# STorM32_NT_breakout_v10.net
KiCad netlist of a schematic drawn in EAGLE
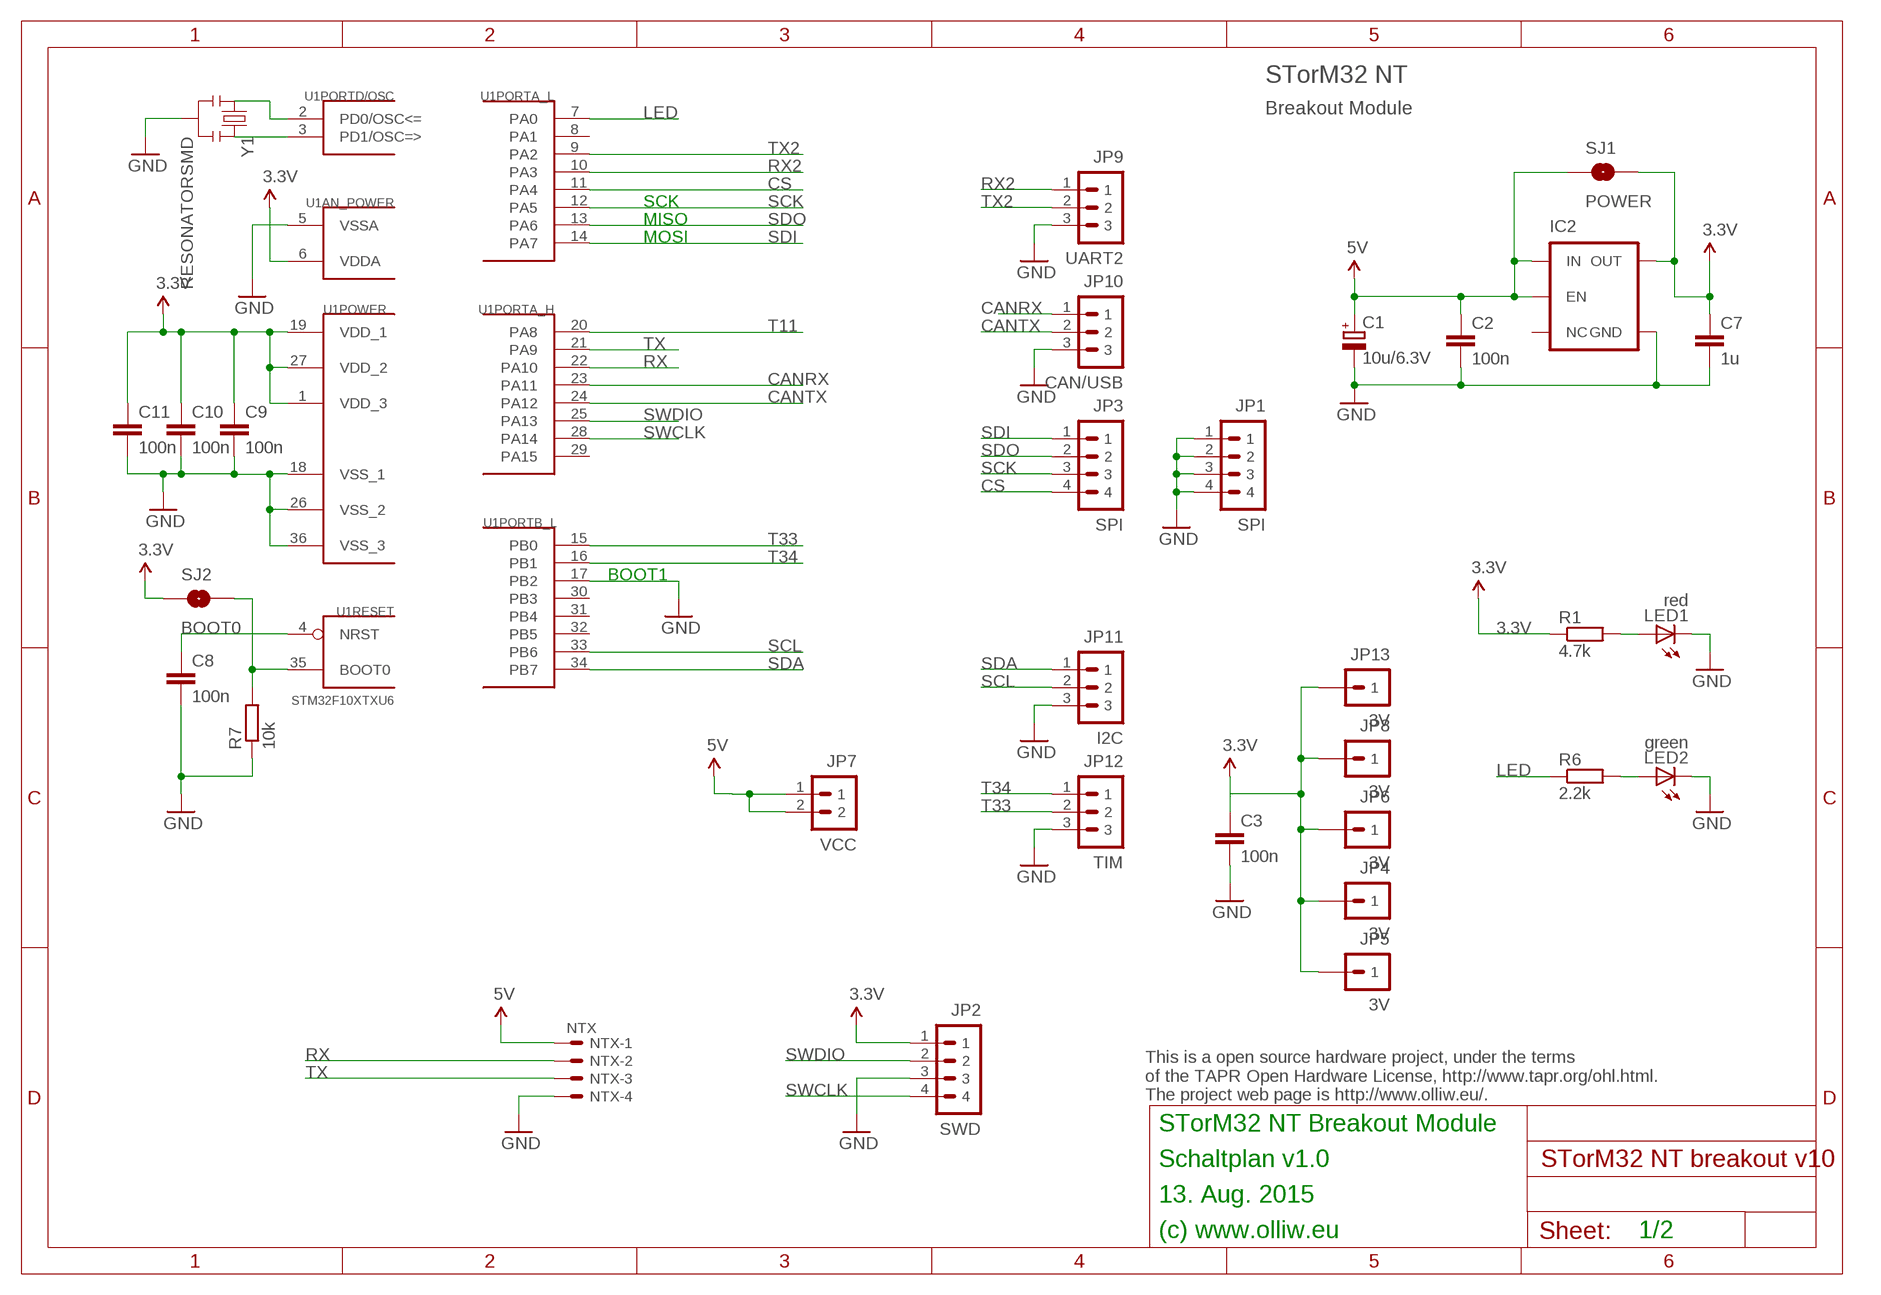
[diagram p0: schematic, sheet 1]

(export (version "E")
  (design (tool "Eeschema 10.0.6"))
  (components
    (comp (ref "C1")
      (value "10u/6.3V")
      (footprint "eagle-import:SMC_B")
      (libsource (lib "eagle-import") (part "CPOL-EUSMCB"))
    )
    (comp (ref "C2")
      (value "100n")
      (footprint "eagle-import:C0603")
      (libsource (lib "eagle-import") (part "C-EUC0603"))
    )
    (comp (ref "C3")
      (value "100n")
      (footprint "eagle-import:C0603")
      (libsource (lib "eagle-import") (part "C-EUC0603"))
    )
    (comp (ref "C7")
      (value "1u")
      (footprint "eagle-import:C0603")
      (libsource (lib "eagle-import") (part "C-EUC0603"))
    )
    (comp (ref "C8")
      (value "100n")
      (footprint "eagle-import:C0603")
      (libsource (lib "eagle-import") (part "C-EUC0603"))
    )
    (comp (ref "C9")
      (value "100n")
      (footprint "eagle-import:C0603")
      (libsource (lib "eagle-import") (part "C-EUC0603"))
    )
    (comp (ref "C10")
      (value "100n")
      (footprint "eagle-import:C0603")
      (libsource (lib "eagle-import") (part "C-EUC0603"))
    )
    (comp (ref "C11")
      (value "100n")
      (footprint "eagle-import:C0603")
      (libsource (lib "eagle-import") (part "C-EUC0603"))
    )
    (comp (ref "IC2")
      (value "V_REG_TPS76433SOT23-5")
      (footprint "eagle-import:SOT23-5")
      (libsource (lib "eagle-import") (part "V_REG_TPS76433SOT23-5"))
    )
    (comp (ref "JP1")
      (value "SPI")
      (footprint "eagle-import:4X1_1P27_OCT_BILEX")
      (libsource (lib "eagle-import") (part "P4X1_1P27-OCT_BILEX"))
    )
    (comp (ref "JP2")
      (value "SWD")
      (footprint "eagle-import:4X1_1P27_OCT_BILEX")
      (libsource (lib "eagle-import") (part "P4X1_1P27-OCT_BILEX"))
    )
    (comp (ref "JP3")
      (value "SPI")
      (footprint "eagle-import:4X1_1P27_OCT_BILEX")
      (libsource (lib "eagle-import") (part "P4X1_1P27-OCT_BILEX"))
    )
    (comp (ref "JP4")
      (value "3V")
      (footprint "eagle-import:1X1_1P27_QUAD_1.0X0.6")
      (libsource (lib "eagle-import") (part "P1X1_1P27-QUAD_1.0X0.6"))
    )
    (comp (ref "JP5")
      (value "3V")
      (footprint "eagle-import:1X1_1P27_QUAD_1.0X0.6")
      (libsource (lib "eagle-import") (part "P1X1_1P27-QUAD_1.0X0.6"))
    )
    (comp (ref "JP6")
      (value "3V")
      (footprint "eagle-import:1X1_1P27_QUAD_1.0X0.6")
      (libsource (lib "eagle-import") (part "P1X1_1P27-QUAD_1.0X0.6"))
    )
    (comp (ref "JP7")
      (value "VCC")
      (footprint "eagle-import:2X1_1P27_OCT_BILEX")
      (libsource (lib "eagle-import") (part "P2X1_1P27-OCT_BILEX"))
    )
    (comp (ref "JP8")
      (value "3V")
      (footprint "eagle-import:1X1_1P27_QUAD_1.0X0.6")
      (libsource (lib "eagle-import") (part "P1X1_1P27-QUAD_1.0X0.6"))
    )
    (comp (ref "JP9")
      (value "UART2")
      (footprint "eagle-import:3X1_1P27_OCT_BILEX")
      (libsource (lib "eagle-import") (part "P3X1_1P27-OCT_BILEX"))
    )
    (comp (ref "JP10")
      (value "CAN/USB")
      (footprint "eagle-import:3X1_1P27_OCT_BILEX")
      (libsource (lib "eagle-import") (part "P3X1_1P27-OCT_BILEX"))
    )
    (comp (ref "JP11")
      (value "I2C")
      (footprint "eagle-import:3X1_1P27_OCT_BILEX")
      (libsource (lib "eagle-import") (part "P3X1_1P27-OCT_BILEX"))
    )
    (comp (ref "JP12")
      (value "TIM")
      (footprint "eagle-import:3X1_1P27_OCT_BILEX")
      (libsource (lib "eagle-import") (part "P3X1_1P27-OCT_BILEX"))
    )
    (comp (ref "JP13")
      (value "3V")
      (footprint "eagle-import:1X1_1P27_QUAD_1.0X0.6")
      (libsource (lib "eagle-import") (part "P1X1_1P27-QUAD_1.0X0.6"))
    )
    (comp (ref "LED1")
      (value "red")
      (footprint "eagle-import:CHIPLED_0603")
      (libsource (lib "eagle-import") (part "LEDCHIPLED_0603"))
    )
    (comp (ref "LED2")
      (value "green")
      (footprint "eagle-import:CHIPLED_0603")
      (libsource (lib "eagle-import") (part "LEDCHIPLED_0603"))
    )
    (comp (ref "NTX")
      (value "NTX")
      (footprint "eagle-import:SM04B-SRSS-TB")
      (libsource (lib "eagle-import") (part "?M04B-SRSS-TBS"))
    )
    (comp (ref "R1")
      (value "4.7k")
      (footprint "eagle-import:R0603")
      (libsource (lib "eagle-import") (part "R-EU_R0603"))
    )
    (comp (ref "R6")
      (value "2.2k")
      (footprint "eagle-import:R0603")
      (libsource (lib "eagle-import") (part "R-EU_R0603"))
    )
    (comp (ref "R7")
      (value "10k")
      (footprint "eagle-import:R0603")
      (libsource (lib "eagle-import") (part "R-EU_R0603"))
    )
    (comp (ref "SJ1")
      (value "POWER")
      (footprint "eagle-import:SJ_2S-NO")
      (libsource (lib "eagle-import") (part "SOLDERJUMPERNO"))
    )
    (comp (ref "SJ2")
      (value "BOOT0")
      (footprint "eagle-import:SJ_2S-NO")
      (libsource (lib "eagle-import") (part "SOLDERJUMPERNO"))
    )
    (comp (ref "U1")
      (value "STM32F10XTXU6")
      (footprint "eagle-import:VFQFPN36")
      (libsource (lib "eagle-import") (part "STM32F10XTXU6"))
    )
    (comp (ref "Y1")
      (value "RESONATORSMD")
      (footprint "eagle-import:RESONATOR-SMD")
      (libsource (lib "eagle-import") (part "RESONATORSMD"))
    )
  )
  (nets
    (net (code "1") (name "/CANRX") (class "Default")
      (node (ref "JP10") (pin "1") (pinfunction "1_1") (pintype "passive"))
      (node (ref "U1") (pin "23") (pinfunction "PA11_23") (pintype "bidirectional"))
    )
    (net (code "2") (name "/CANTX") (class "Default")
      (node (ref "JP10") (pin "2") (pinfunction "2_2") (pintype "passive"))
      (node (ref "U1") (pin "24") (pinfunction "PA12_24") (pintype "bidirectional"))
    )
    (net (code "3") (name "/CS") (class "Default")
      (node (ref "JP3") (pin "4") (pinfunction "4_4") (pintype "passive"))
      (node (ref "U1") (pin "11") (pinfunction "PA4_11") (pintype "bidirectional"))
    )
    (net (code "4") (name "/LED") (class "Default")
      (node (ref "R6") (pin "1") (pinfunction "1_1") (pintype "passive"))
      (node (ref "U1") (pin "7") (pinfunction "PA0_7") (pintype "bidirectional"))
    )
    (net (code "5") (name "/RX") (class "Default")
      (node (ref "NTX") (pin "2") (pinfunction "S_2") (pintype "passive"))
      (node (ref "U1") (pin "22") (pinfunction "PA10_22") (pintype "bidirectional"))
    )
    (net (code "6") (name "/RX2") (class "Default")
      (node (ref "JP9") (pin "1") (pinfunction "1_1") (pintype "passive"))
      (node (ref "U1") (pin "10") (pinfunction "PA3_10") (pintype "bidirectional"))
    )
    (net (code "7") (name "/SCK") (class "Default")
      (node (ref "JP3") (pin "3") (pinfunction "3_3") (pintype "passive"))
      (node (ref "U1") (pin "12") (pinfunction "PA5_12") (pintype "bidirectional"))
    )
    (net (code "8") (name "/SCL") (class "Default")
      (node (ref "JP11") (pin "2") (pinfunction "2_2") (pintype "passive"))
      (node (ref "U1") (pin "33") (pinfunction "PB6_33") (pintype "bidirectional"))
    )
    (net (code "9") (name "/SDA") (class "Default")
      (node (ref "JP11") (pin "1") (pinfunction "1_1") (pintype "passive"))
      (node (ref "U1") (pin "34") (pinfunction "PB7_34") (pintype "bidirectional"))
    )
    (net (code "10") (name "/SDI") (class "Default")
      (node (ref "JP3") (pin "1") (pinfunction "1_1") (pintype "passive"))
      (node (ref "U1") (pin "14") (pinfunction "PA7_14") (pintype "bidirectional"))
    )
    (net (code "11") (name "/SDO") (class "Default")
      (node (ref "JP3") (pin "2") (pinfunction "2_2") (pintype "passive"))
      (node (ref "U1") (pin "13") (pinfunction "PA6_13") (pintype "bidirectional"))
    )
    (net (code "12") (name "/SWCLK") (class "Default")
      (node (ref "JP2") (pin "4") (pinfunction "4_4") (pintype "passive"))
      (node (ref "U1") (pin "28") (pinfunction "PA14_28") (pintype "bidirectional"))
    )
    (net (code "13") (name "/SWDIO") (class "Default")
      (node (ref "JP2") (pin "2") (pinfunction "2_2") (pintype "passive"))
      (node (ref "U1") (pin "25") (pinfunction "PA13_25") (pintype "bidirectional"))
    )
    (net (code "14") (name "/T11") (class "Default")
      (node (ref "U1") (pin "20") (pinfunction "PA8_20") (pintype "bidirectional"))
    )
    (net (code "15") (name "/T33") (class "Default")
      (node (ref "JP12") (pin "2") (pinfunction "2_2") (pintype "passive"))
      (node (ref "U1") (pin "15") (pinfunction "PB0_15") (pintype "bidirectional"))
    )
    (net (code "16") (name "/T34") (class "Default")
      (node (ref "JP12") (pin "1") (pinfunction "1_1") (pintype "passive"))
      (node (ref "U1") (pin "16") (pinfunction "PB1_16") (pintype "bidirectional"))
    )
    (net (code "17") (name "/TX") (class "Default")
      (node (ref "NTX") (pin "3") (pinfunction "S_3") (pintype "passive"))
      (node (ref "U1") (pin "21") (pinfunction "PA9_21") (pintype "bidirectional"))
    )
    (net (code "18") (name "/TX2") (class "Default")
      (node (ref "JP9") (pin "2") (pinfunction "2_2") (pintype "passive"))
      (node (ref "U1") (pin "9") (pinfunction "PA2_9") (pintype "bidirectional"))
    )
    (net (code "19") (name "3.3V") (class "Default")
      (node (ref "C10") (pin "1") (pinfunction "1_1") (pintype "passive"))
      (node (ref "C11") (pin "1") (pinfunction "1_1") (pintype "passive"))
      (node (ref "C3") (pin "1") (pinfunction "1_1") (pintype "passive"))
      (node (ref "C7") (pin "1") (pinfunction "1_1") (pintype "passive"))
      (node (ref "C9") (pin "1") (pinfunction "1_1") (pintype "passive"))
      (node (ref "IC2") (pin "5") (pinfunction "OUT_5") (pintype "passive"))
      (node (ref "JP13") (pin "1") (pinfunction "1_1") (pintype "passive"))
      (node (ref "JP2") (pin "1") (pinfunction "1_1") (pintype "passive"))
      (node (ref "JP4") (pin "1") (pinfunction "1_1") (pintype "passive"))
      (node (ref "JP5") (pin "1") (pinfunction "1_1") (pintype "passive"))
      (node (ref "JP6") (pin "1") (pinfunction "1_1") (pintype "passive"))
      (node (ref "JP8") (pin "1") (pinfunction "1_1") (pintype "passive"))
      (node (ref "R1") (pin "1") (pinfunction "1_1") (pintype "passive"))
      (node (ref "SJ1") (pin "2") (pinfunction "2_2") (pintype "passive"))
      (node (ref "SJ2") (pin "1") (pinfunction "1_1") (pintype "passive"))
      (node (ref "U1") (pin "1") (pinfunction "VDD_3_1") (pintype "power_in"))
      (node (ref "U1") (pin "19") (pinfunction "VDD_1_19") (pintype "power_in"))
      (node (ref "U1") (pin "27") (pinfunction "VDD_2_27") (pintype "power_in"))
      (node (ref "U1") (pin "6") (pinfunction "VDDA_6") (pintype "power_in"))
    )
    (net (code "20") (name "5V") (class "Default")
      (node (ref "C1") (pin "+") (pinfunction "+_+") (pintype "passive"))
      (node (ref "C2") (pin "1") (pinfunction "1_1") (pintype "passive"))
      (node (ref "IC2") (pin "1") (pinfunction "IN_1") (pintype "input"))
      (node (ref "IC2") (pin "3") (pinfunction "EN_3") (pintype "input"))
      (node (ref "JP7") (pin "1") (pinfunction "1_1") (pintype "passive"))
      (node (ref "JP7") (pin "2") (pinfunction "2_2") (pintype "passive"))
      (node (ref "NTX") (pin "1") (pinfunction "S_1") (pintype "passive"))
      (node (ref "SJ1") (pin "1") (pinfunction "1_1") (pintype "passive"))
    )
    (net (code "21") (name "GND") (class "Default")
      (node (ref "C1") (pin "-") (pinfunction "-_-") (pintype "passive"))
      (node (ref "C10") (pin "2") (pinfunction "2_2") (pintype "passive"))
      (node (ref "C11") (pin "2") (pinfunction "2_2") (pintype "passive"))
      (node (ref "C2") (pin "2") (pinfunction "2_2") (pintype "passive"))
      (node (ref "C3") (pin "2") (pinfunction "2_2") (pintype "passive"))
      (node (ref "C7") (pin "2") (pinfunction "2_2") (pintype "passive"))
      (node (ref "C8") (pin "2") (pinfunction "2_2") (pintype "passive"))
      (node (ref "C9") (pin "2") (pinfunction "2_2") (pintype "passive"))
      (node (ref "IC2") (pin "2") (pinfunction "GND_2") (pintype "input"))
      (node (ref "JP1") (pin "1") (pinfunction "1_1") (pintype "passive"))
      (node (ref "JP1") (pin "2") (pinfunction "2_2") (pintype "passive"))
      (node (ref "JP1") (pin "3") (pinfunction "3_3") (pintype "passive"))
      (node (ref "JP1") (pin "4") (pinfunction "4_4") (pintype "passive"))
      (node (ref "JP10") (pin "3") (pinfunction "3_3") (pintype "passive"))
      (node (ref "JP11") (pin "3") (pinfunction "3_3") (pintype "passive"))
      (node (ref "JP12") (pin "3") (pinfunction "3_3") (pintype "passive"))
      (node (ref "JP2") (pin "3") (pinfunction "3_3") (pintype "passive"))
      (node (ref "JP9") (pin "3") (pinfunction "3_3") (pintype "passive"))
      (node (ref "LED1") (pin "C") (pinfunction "C_C") (pintype "passive"))
      (node (ref "LED2") (pin "C") (pinfunction "C_C") (pintype "passive"))
      (node (ref "NTX") (pin "4") (pinfunction "S_4") (pintype "passive"))
      (node (ref "R7") (pin "1") (pinfunction "1_1") (pintype "passive"))
      (node (ref "U1") (pin "17") (pinfunction "PB2_17") (pintype "bidirectional"))
      (node (ref "U1") (pin "18") (pinfunction "VSS_1_18") (pintype "power_in"))
      (node (ref "U1") (pin "26") (pinfunction "VSS_2_26") (pintype "power_in"))
      (node (ref "U1") (pin "36") (pinfunction "VSS_3_36") (pintype "power_in"))
      (node (ref "U1") (pin "5") (pinfunction "VSSA_5") (pintype "power_in"))
      (node (ref "Y1") (pin "2") (pinfunction "2_2") (pintype "passive"))
    )
    (net (code "22") (name "Net-(LED1-PadA)") (class "Default")
      (node (ref "LED1") (pin "A") (pinfunction "A_A") (pintype "passive"))
      (node (ref "R1") (pin "2") (pinfunction "2_2") (pintype "passive"))
    )
    (net (code "23") (name "Net-(LED2-PadA)") (class "Default")
      (node (ref "LED2") (pin "A") (pinfunction "A_A") (pintype "passive"))
      (node (ref "R6") (pin "2") (pinfunction "2_2") (pintype "passive"))
    )
    (net (code "24") (name "Net-(U1E-PD0{slash}OSC<=)") (class "Default")
      (node (ref "U1") (pin "2") (pinfunction "PD0/OSC<=_2") (pintype "bidirectional"))
      (node (ref "Y1") (pin "1") (pinfunction "1_1") (pintype "passive"))
    )
    (net (code "25") (name "Net-(U1E-PD1{slash}OSC=>)") (class "Default")
      (node (ref "U1") (pin "3") (pinfunction "PD1/OSC=>_3") (pintype "bidirectional"))
      (node (ref "Y1") (pin "3") (pinfunction "3_3") (pintype "passive"))
    )
    (net (code "26") (name "Net-(U1G-BOOT0)") (class "Default")
      (node (ref "R7") (pin "2") (pinfunction "2_2") (pintype "passive"))
      (node (ref "SJ2") (pin "2") (pinfunction "2_2") (pintype "passive"))
      (node (ref "U1") (pin "35") (pinfunction "BOOT0_35") (pintype "input"))
    )
    (net (code "27") (name "Net-(U1G-NRST)") (class "Default")
      (node (ref "C8") (pin "1") (pinfunction "1_1") (pintype "passive"))
      (node (ref "U1") (pin "4") (pinfunction "NRST_4") (pintype "input"))
    )
    (net (code "28") (name "unconnected-(IC2-NC-Pad4)") (class "Default")
      (node (ref "IC2") (pin "4") (pinfunction "NC_4") (pintype "input"))
    )
    (net (code "29") (name "unconnected-(U1B-PA15-Pad29)") (class "Default")
      (node (ref "U1") (pin "29") (pinfunction "PA15_29") (pintype "bidirectional"))
    )
    (net (code "30") (name "unconnected-(U1C-PA1-Pad8)") (class "Default")
      (node (ref "U1") (pin "8") (pinfunction "PA1_8") (pintype "bidirectional"))
    )
    (net (code "31") (name "unconnected-(U1D-PB3-Pad30)") (class "Default")
      (node (ref "U1") (pin "30") (pinfunction "PB3_30") (pintype "bidirectional"))
    )
    (net (code "32") (name "unconnected-(U1D-PB4-Pad31)") (class "Default")
      (node (ref "U1") (pin "31") (pinfunction "PB4_31") (pintype "bidirectional"))
    )
    (net (code "33") (name "unconnected-(U1D-PB5-Pad32)") (class "Default")
      (node (ref "U1") (pin "32") (pinfunction "PB5_32") (pintype "bidirectional"))
    )
  )
)
